# Amp2.net
KiCad netlist of a schematic drawn in EasyEDA
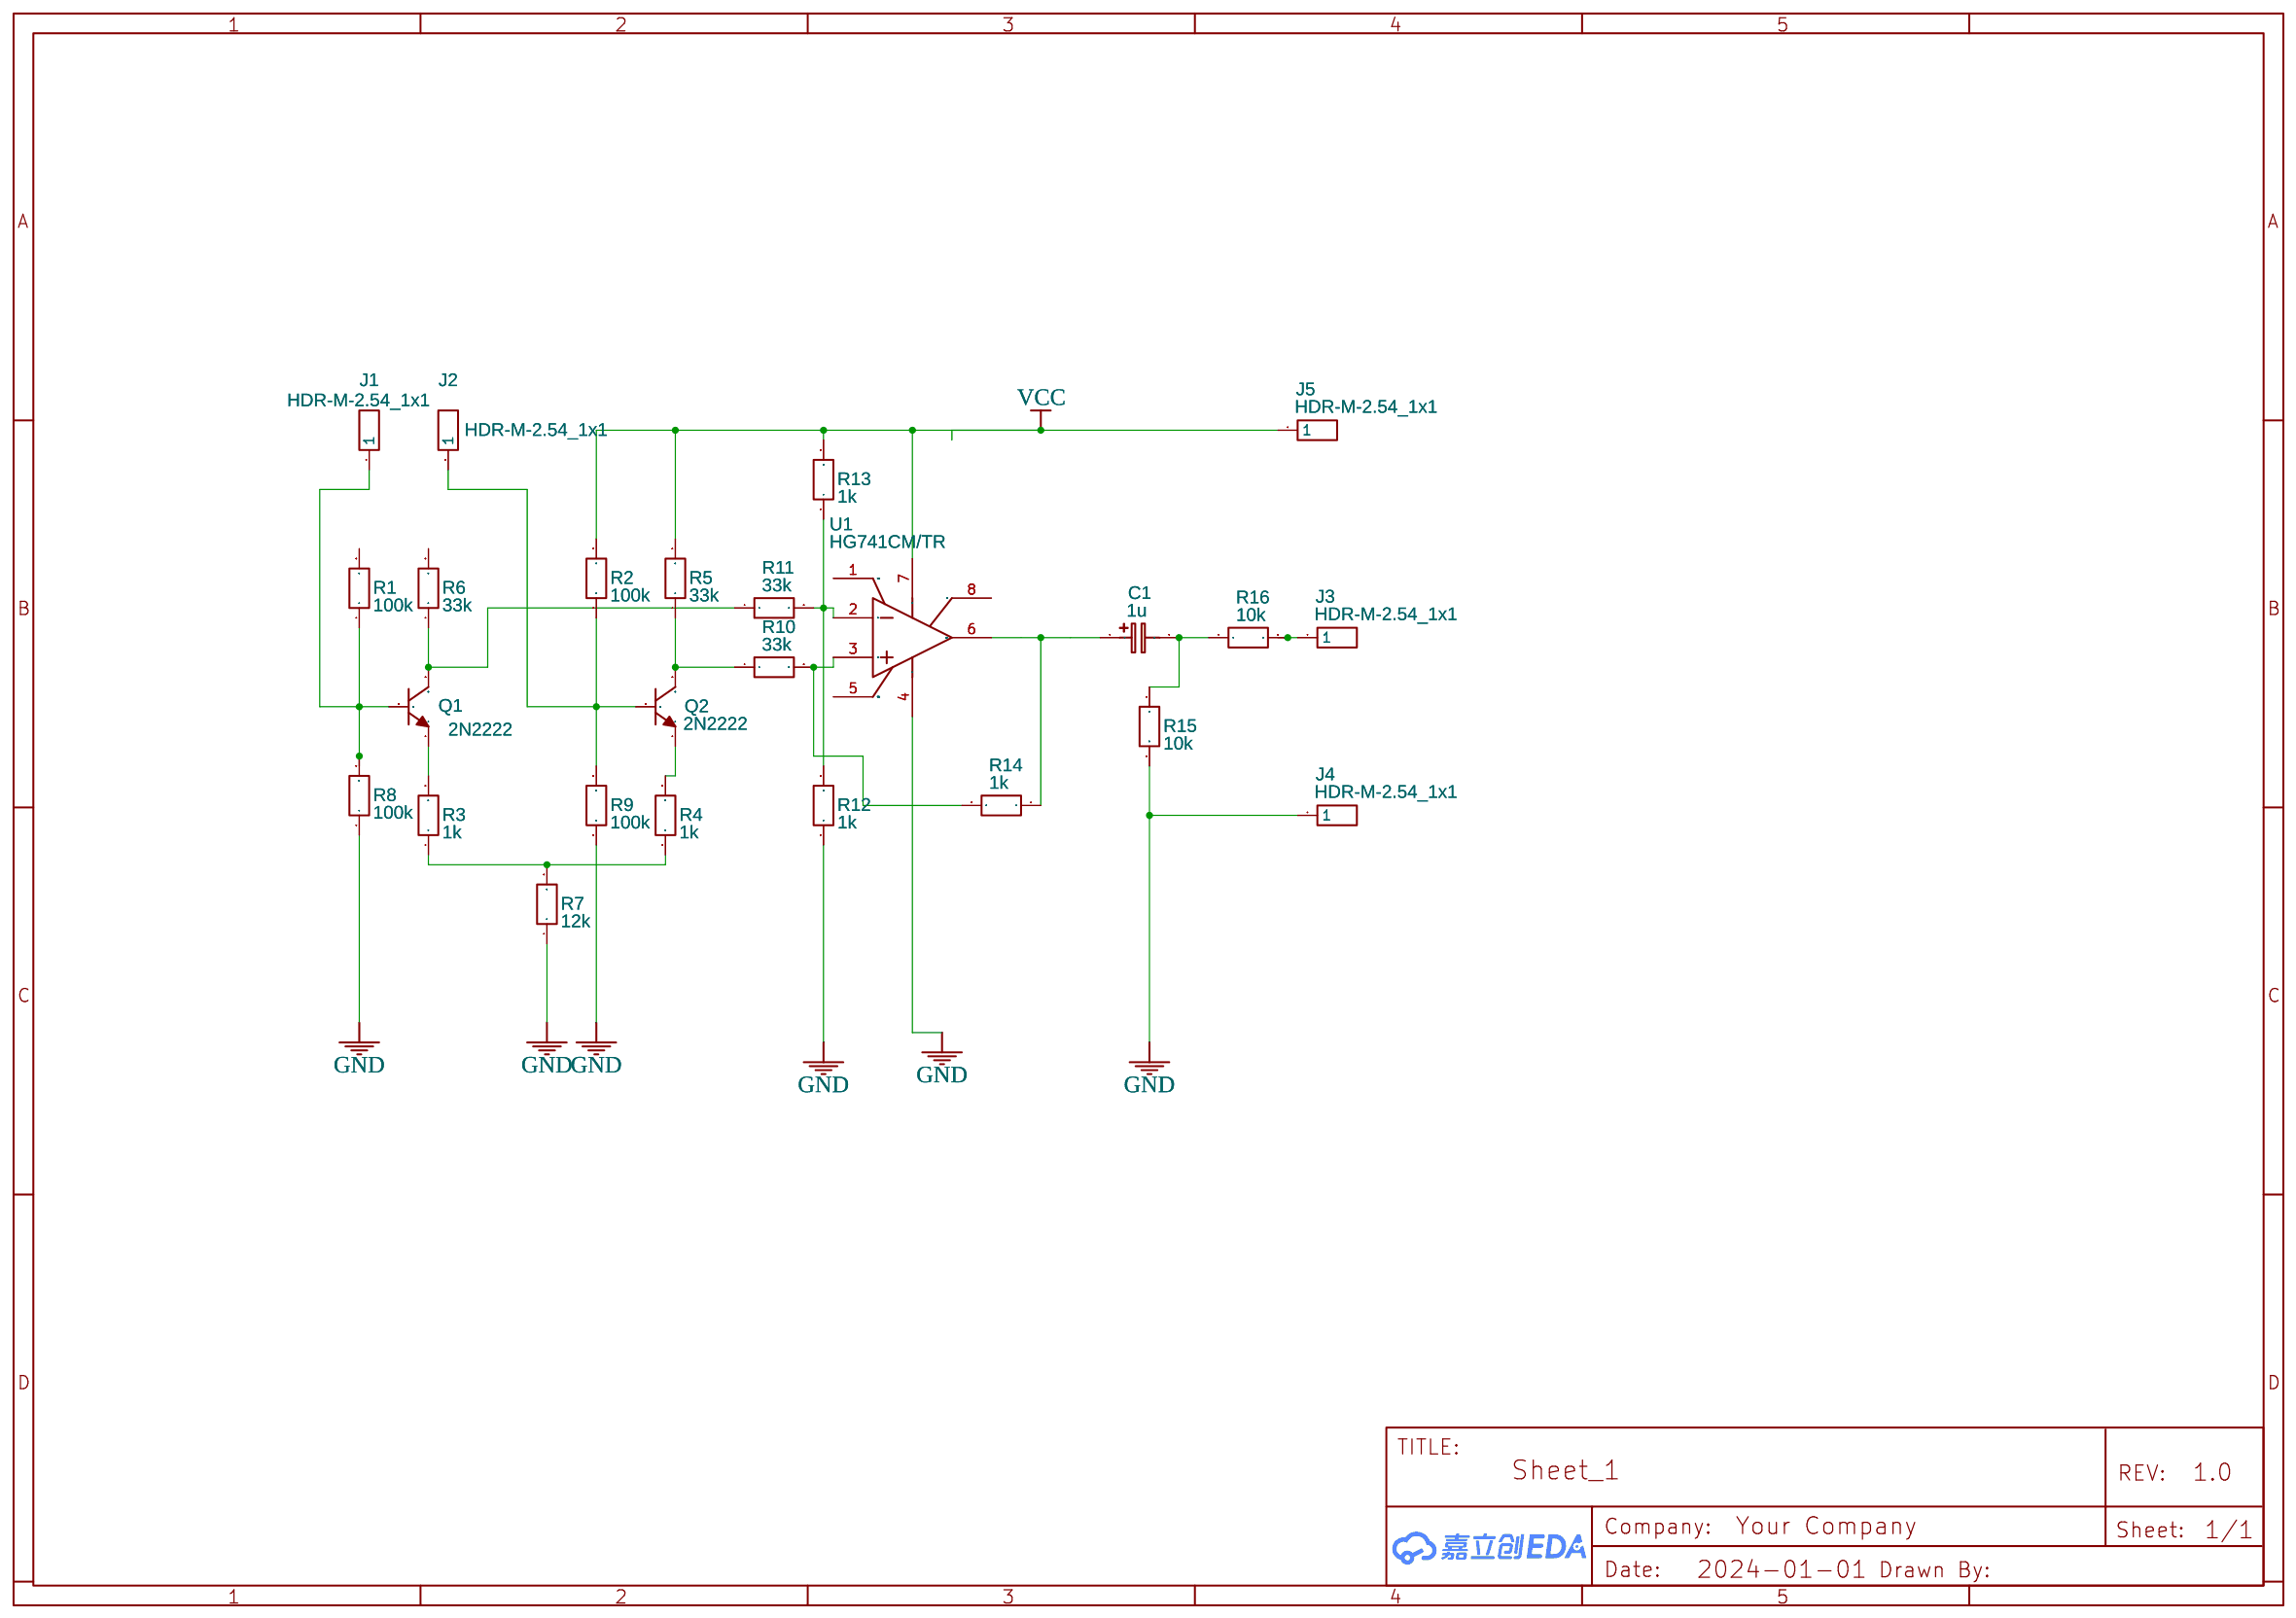
[diagram p0: schematic sheet]

(export (version "E")
  (design (tool "Eeschema 10.0.6"))
  (components
    (comp (ref "C1") (value "1u") (libsource (lib "") (part "C_Tan_SMD_A_EU")))
    (comp (ref "J1")
      (value "HDR-M-2.54_1x1")
      (fields (field (name "BOM_Supplier Part") "C81276"))
      (libsource (lib "") (part "HDR-M-2.54_1x1_1"))
    )
    (comp (ref "J2")
      (value "HDR-M-2.54_1x1")
      (fields (field (name "BOM_Supplier Part") "C81276"))
      (libsource (lib "") (part "HDR-M-2.54_1x1_1"))
    )
    (comp (ref "J3")
      (value "HDR-M-2.54_1x1")
      (fields (field (name "BOM_Supplier Part") "C81276"))
      (libsource (lib "") (part "HDR-M-2.54_1x1"))
    )
    (comp (ref "J4")
      (value "HDR-M-2.54_1x1")
      (fields (field (name "BOM_Supplier Part") "C81276"))
      (libsource (lib "") (part "HDR-M-2.54_1x1"))
    )
    (comp (ref "J5")
      (value "HDR-M-2.54_1x1")
      (fields (field (name "BOM_Supplier Part") "C81276"))
      (libsource (lib "") (part "HDR-M-2.54_1x1"))
    )
    (comp (ref "Q1")
      (value "2N2222")
      (fields
        (field (name "BOM_Manufacturer Part") "2n3904S-RTK/PS")
        (field (name "BOM_Supplier Part") "C18536")
      )
      (libsource (lib "") (part "2N3904(SOT-23)"))
    )
    (comp (ref "Q2")
      (value "2N2222")
      (fields
        (field (name "BOM_Manufacturer Part") "2n3904S-RTK/PS")
        (field (name "BOM_Supplier Part") "C18536")
      )
      (libsource (lib "") (part "2N3904(SOT-23)"))
    )
    (comp (ref "R1") (value "100k") (libsource (lib "") (part "R_0603_EU_1")))
    (comp (ref "R2") (value "100k") (libsource (lib "") (part "R_0603_EU_1")))
    (comp (ref "R3") (value "1k") (libsource (lib "") (part "R_0603_EU_1")))
    (comp (ref "R4") (value "1k") (libsource (lib "") (part "R_0603_EU_1")))
    (comp (ref "R5") (value "33k") (libsource (lib "") (part "R_0603_EU_1")))
    (comp (ref "R6") (value "33k") (libsource (lib "") (part "R_0603_EU_1")))
    (comp (ref "R7") (value "12k") (libsource (lib "") (part "R_0603_EU_1")))
    (comp (ref "R8") (value "100k") (libsource (lib "") (part "R_0603_EU_1")))
    (comp (ref "R9") (value "100k") (libsource (lib "") (part "R_0603_EU_1")))
    (comp (ref "R10") (value "33k") (libsource (lib "") (part "R_0603_EU")))
    (comp (ref "R11") (value "33k") (libsource (lib "") (part "R_0603_EU")))
    (comp (ref "R12") (value "1k") (libsource (lib "") (part "R_0603_EU_1")))
    (comp (ref "R13") (value "1k") (libsource (lib "") (part "R_0603_EU_1")))
    (comp (ref "R14") (value "1k") (libsource (lib "") (part "R_0603_EU_3")))
    (comp (ref "R15") (value "10k") (libsource (lib "") (part "R_0603_EU_2")))
    (comp (ref "R16") (value "10k") (libsource (lib "") (part "R_0603_EU")))
    (comp (ref "U1")
      (value "HG741CM/TR")
      (fields (field (name "Manufacturer") "HGSEMI(华冠)"))
      (libsource (lib "") (part "HG741CM/TR"))
    )
  )
  (nets
    (net (code "1") (name "GND") (class "Default")
      (node (ref "J4") (pin "1") (pinfunction "1_1") (pintype "input"))
      (node (ref "R12") (pin "1") (pinfunction "1_1") (pintype "unspecified"))
      (node (ref "R15") (pin "2") (pinfunction "2_2") (pintype "unspecified"))
      (node (ref "R7") (pin "1") (pinfunction "1_1") (pintype "unspecified"))
      (node (ref "R8") (pin "1") (pinfunction "1_1") (pintype "unspecified"))
      (node (ref "R9") (pin "1") (pinfunction "1_1") (pintype "unspecified"))
      (node (ref "U1") (pin "4") (pinfunction "V-_4") (pintype "passive"))
    )
    (net (code "2") (name "Net-(C1-Pad2)") (class "Default")
      (node (ref "C1") (pin "2") (pinfunction "2_2") (pintype "unspecified"))
      (node (ref "R15") (pin "1") (pinfunction "1_1") (pintype "unspecified"))
      (node (ref "R16") (pin "1") (pinfunction "1_1") (pintype "unspecified"))
    )
    (net (code "3") (name "Net-(J3-Pad1)") (class "Default")
      (node (ref "J3") (pin "1") (pinfunction "1_1") (pintype "input"))
      (node (ref "R16") (pin "2") (pinfunction "2_2") (pintype "unspecified"))
    )
    (net (code "4") (name "Net-(Q1-B)") (class "Default")
      (node (ref "J1") (pin "1") (pinfunction "1_1") (pintype "input"))
      (node (ref "Q1") (pin "2") (pinfunction "B_2") (pintype "input"))
      (node (ref "R1") (pin "1") (pinfunction "1_1") (pintype "unspecified"))
      (node (ref "R8") (pin "2") (pinfunction "2_2") (pintype "unspecified"))
    )
    (net (code "5") (name "Net-(Q1-C)") (class "Default")
      (node (ref "Q1") (pin "3") (pinfunction "C_3") (pintype "input"))
      (node (ref "R11") (pin "1") (pinfunction "1_1") (pintype "unspecified"))
      (node (ref "R6") (pin "1") (pinfunction "1_1") (pintype "unspecified"))
    )
    (net (code "6") (name "Net-(Q1-E)") (class "Default")
      (node (ref "Q1") (pin "1") (pinfunction "E_1") (pintype "input"))
      (node (ref "R3") (pin "2") (pinfunction "2_2") (pintype "unspecified"))
    )
    (net (code "7") (name "Net-(Q2-B)") (class "Default")
      (node (ref "J2") (pin "1") (pinfunction "1_1") (pintype "input"))
      (node (ref "Q2") (pin "2") (pinfunction "B_2") (pintype "input"))
      (node (ref "R2") (pin "1") (pinfunction "1_1") (pintype "unspecified"))
      (node (ref "R9") (pin "2") (pinfunction "2_2") (pintype "unspecified"))
    )
    (net (code "8") (name "Net-(Q2-C)") (class "Default")
      (node (ref "Q2") (pin "3") (pinfunction "C_3") (pintype "input"))
      (node (ref "R10") (pin "1") (pinfunction "1_1") (pintype "unspecified"))
      (node (ref "R5") (pin "1") (pinfunction "1_1") (pintype "unspecified"))
    )
    (net (code "9") (name "Net-(Q2-E)") (class "Default")
      (node (ref "Q2") (pin "1") (pinfunction "E_1") (pintype "input"))
      (node (ref "R4") (pin "2") (pinfunction "2_2") (pintype "unspecified"))
    )
    (net (code "10") (name "Net-(R3-Pad1)") (class "Default")
      (node (ref "R3") (pin "1") (pinfunction "1_1") (pintype "unspecified"))
      (node (ref "R4") (pin "1") (pinfunction "1_1") (pintype "unspecified"))
      (node (ref "R7") (pin "2") (pinfunction "2_2") (pintype "unspecified"))
    )
    (net (code "11") (name "Net-(U1-+IN)") (class "Default")
      (node (ref "R10") (pin "2") (pinfunction "2_2") (pintype "unspecified"))
      (node (ref "R14") (pin "2") (pinfunction "2_2") (pintype "unspecified"))
      (node (ref "U1") (pin "3") (pinfunction "+IN_3") (pintype "unspecified"))
    )
    (net (code "12") (name "Net-(U1--IN)") (class "Default")
      (node (ref "R11") (pin "2") (pinfunction "2_2") (pintype "unspecified"))
      (node (ref "R12") (pin "2") (pinfunction "2_2") (pintype "unspecified"))
      (node (ref "R13") (pin "1") (pinfunction "1_1") (pintype "unspecified"))
      (node (ref "U1") (pin "2") (pinfunction "-IN_2") (pintype "unspecified"))
    )
    (net (code "13") (name "Net-(U1-OUTPUT)") (class "Default")
      (node (ref "C1") (pin "1") (pinfunction "1_1") (pintype "unspecified"))
      (node (ref "R14") (pin "1") (pinfunction "1_1") (pintype "unspecified"))
      (node (ref "U1") (pin "6") (pinfunction "OUTPUT_6") (pintype "unspecified"))
    )
    (net (code "14") (name "VCC") (class "Default")
      (node (ref "J5") (pin "1") (pinfunction "1_1") (pintype "input"))
      (node (ref "R13") (pin "2") (pinfunction "2_2") (pintype "unspecified"))
      (node (ref "R2") (pin "2") (pinfunction "2_2") (pintype "unspecified"))
      (node (ref "R5") (pin "2") (pinfunction "2_2") (pintype "unspecified"))
      (node (ref "U1") (pin "7") (pinfunction "V+_7") (pintype "passive"))
    )
    (net (code "15") (name "unconnected-(R1-Pad2)") (class "Default")
      (node (ref "R1") (pin "2") (pinfunction "2_2") (pintype "unspecified"))
    )
    (net (code "16") (name "unconnected-(R6-Pad2)") (class "Default")
      (node (ref "R6") (pin "2") (pinfunction "2_2") (pintype "unspecified"))
    )
    (net (code "17") (name "unconnected-(U1-NC-Pad8)") (class "Default")
      (node (ref "U1") (pin "8") (pinfunction "NC_8") (pintype "unspecified"))
    )
    (net (code "18") (name "unconnected-(U1-OFFSET_NULL-Pad1)") (class "Default")
      (node (ref "U1") (pin "1") (pinfunction "OFFSET_NULL_1") (pintype "unspecified"))
    )
    (net (code "19") (name "unconnected-(U1-OFFSET_NULL-Pad5)") (class "Default")
      (node (ref "U1") (pin "5") (pinfunction "OFFSET_NULL_5") (pintype "unspecified"))
    )
  )
)
